# Power.net
KiCad netlist of a schematic drawn in Altium Designer
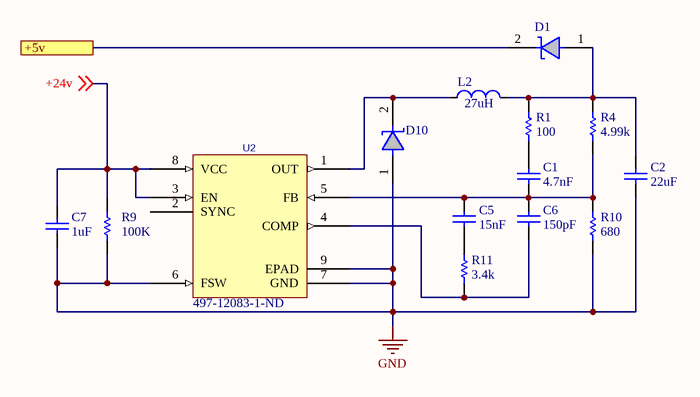
[diagram p0: Power.SchDoc]

(export (version "E")
  (design (tool "Eeschema 10.0.6"))
  (components
    (comp (ref "C1")
      (value "4.7nF")
      (footprint "0603")
      (description "4.7nF 10% 50V")
      (fields (field (name "TOLERANCE") "10%") (field (name "VOLTAGE") "50V"))
      (libsource (lib "CPHComponentSource") (part "CAP_2"))
    )
    (comp (ref "C2")
      (value "22uF")
      (footprint "0603")
      (description "22uF 20% 6.3V")
      (fields (field (name "TOLERANCE") "20%") (field (name "VOLTAGE") "6.3V"))
      (libsource (lib "CPHComponentSource") (part "CAP_1_25"))
    )
    (comp (ref "C5")
      (value "15nF")
      (footprint "0603")
      (description "15nF 10% 50V")
      (fields (field (name "TOLERANCE") "10%") (field (name "VOLTAGE") "50V"))
      (libsource (lib "CPHComponentSource") (part "CAP_1_17"))
    )
    (comp (ref "C6")
      (value "150pF")
      (footprint "0402")
      (description "150pF 5% 50V")
      (fields (field (name "TOLERANCE") "5%") (field (name "VOLTAGE") "50V"))
      (libsource (lib "CPHComponentSource") (part "CAP_1_16"))
    )
    (comp (ref "C7")
      (value "1uF")
      (footprint "0402")
      (description "1uF 10% 50V")
      (fields (field (name "Comment") "CAP_1_21_3"))
      (libsource (lib "CPHComponentSource") (part "CAP_1_21_3"))
    )
    (comp (ref "D1")
      (value "SCHOTTKY DIODE")
      (footprint "SOD323")
      (libsource (lib "CPHComponentSource") (part "SCHOTTKY DIODE"))
    )
    (comp (ref "D10")
      (value "SCHOTTKY DIODE")
      (footprint "SOD323")
      (libsource (lib "") (part "SCHOTTKY DIODE_1"))
    )
    (comp (ref "L2")
      (value "INDUCTOR")
      (footprint "0603")
      (fields (field (name "INDUCTANCE") "27uH"))
      (libsource (lib "CPHComponentSource") (part "INDUCTOR"))
    )
    (comp (ref "R1")
      (value "100")
      (footprint "0603")
      (description "RES 100 0.1W ±1% 0603 (1608)")
      (fields (field (name "Comment") "RES_9"))
      (libsource (lib "CPHComponentSource") (part "RES_9"))
    )
    (comp (ref "R4")
      (value "4.99k")
      (footprint "0402")
      (description "RES 4.99K ±1% 0603 (1608)")
      (fields (field (name "Comment") "RES_38"))
      (libsource (lib "CPHComponentSource") (part "RES_38"))
    )
    (comp (ref "R9")
      (value "100K")
      (footprint "0402")
      (description "RES 100K 0.1W ±1% 0603 (1608 Metric)")
      (fields (field (name "Comment") "RES_11"))
      (libsource (lib "CPHComponentSource") (part "RES_11"))
    )
    (comp (ref "R10")
      (value "680")
      (footprint "0402")
      (description "RES 680 ±1% 0603 (1608)")
      (fields (field (name "Comment") "RES_49"))
      (libsource (lib "CPHComponentSource") (part "RES_49"))
    )
    (comp (ref "R11")
      (value "3.4k")
      (footprint "0603")
      (description "RES 3.4K ±1% 0603 (1608)")
      (fields (field (name "Comment") "RES_32"))
      (libsource (lib "CPHComponentSource") (part "RES_32"))
    )
    (comp (ref "U2")
      (value "L7986ATR")
      (footprint "L7986ATR")
      (description "IC Switching Regulator 3A STEP-DOWN 8-HSOP")
      (fields (field (name "SUPPLIER PART NUMBER 1") "497-12083-1-ND"))
      (libsource (lib "CPHComponentSource") (part "L7986ATR"))
    )
  )
  (nets
    (net (code "1") (name "+24v") (class "Default")
      (node (ref "C7") (pin "2") (pinfunction "2_2") (pintype "passive"))
      (node (ref "R9") (pin "1") (pinfunction "1_1") (pintype "passive"))
      (node (ref "U2") (pin "3") (pinfunction "EN_3") (pintype "input"))
      (node (ref "U2") (pin "8") (pinfunction "VCC_8") (pintype "input"))
    )
    (net (code "2") (name "/+5v") (class "Default")
      (node (ref "D1") (pin "2") (pinfunction "K_2") (pintype "passive"))
    )
    (net (code "3") (name "GND") (class "Default")
      (node (ref "C2") (pin "1") (pinfunction "1_1") (pintype "passive"))
      (node (ref "C7") (pin "1") (pinfunction "1_1") (pintype "passive"))
      (node (ref "D10") (pin "1") (pinfunction "A_1") (pintype "passive"))
      (node (ref "R10") (pin "1") (pinfunction "1_1") (pintype "passive"))
      (node (ref "R9") (pin "2") (pinfunction "2_2") (pintype "passive"))
      (node (ref "U2") (pin "6") (pinfunction "FSW_6") (pintype "input"))
      (node (ref "U2") (pin "7") (pinfunction "GND_7") (pintype "power_in"))
      (node (ref "U2") (pin "9") (pinfunction "EPAD_9") (pintype "power_in"))
    )
    (net (code "4") (name "Net-(C1-Pad1)") (class "Default")
      (node (ref "C1") (pin "1") (pinfunction "1_1") (pintype "passive"))
      (node (ref "R1") (pin "1") (pinfunction "1_1") (pintype "passive"))
    )
    (net (code "5") (name "Net-(C5-Pad1)") (class "Default")
      (node (ref "C5") (pin "1") (pinfunction "1_1") (pintype "passive"))
      (node (ref "R11") (pin "2") (pinfunction "2_2") (pintype "passive"))
    )
    (net (code "6") (name "Net-(D1-A)") (class "Default")
      (node (ref "C2") (pin "2") (pinfunction "2_2") (pintype "passive"))
      (node (ref "D1") (pin "1") (pinfunction "A_1") (pintype "passive"))
      (node (ref "L2") (pin "2") (pintype "passive"))
      (node (ref "R1") (pin "2") (pinfunction "2_2") (pintype "passive"))
      (node (ref "R4") (pin "2") (pinfunction "2_2") (pintype "passive"))
    )
    (net (code "7") (name "Net-(D10-K)") (class "Default")
      (node (ref "D10") (pin "2") (pinfunction "K_2") (pintype "passive"))
      (node (ref "L2") (pin "1") (pintype "passive"))
      (node (ref "U2") (pin "1") (pinfunction "OUT_1") (pintype "output"))
    )
    (net (code "8") (name "Net-(U2-COMP)") (class "Default")
      (node (ref "C6") (pin "1") (pinfunction "1_1") (pintype "passive"))
      (node (ref "R11") (pin "1") (pinfunction "1_1") (pintype "passive"))
      (node (ref "U2") (pin "4") (pinfunction "COMP_4") (pintype "output"))
    )
    (net (code "9") (name "Net-(U2-FB)") (class "Default")
      (node (ref "C1") (pin "2") (pinfunction "2_2") (pintype "passive"))
      (node (ref "C5") (pin "2") (pinfunction "2_2") (pintype "passive"))
      (node (ref "C6") (pin "2") (pinfunction "2_2") (pintype "passive"))
      (node (ref "R10") (pin "2") (pinfunction "2_2") (pintype "passive"))
      (node (ref "R4") (pin "1") (pinfunction "1_1") (pintype "passive"))
      (node (ref "U2") (pin "5") (pinfunction "FB_5") (pintype "input"))
    )
    (net (code "10") (name "unconnected-(U2-SYNC-Pad2)") (class "Default")
      (node (ref "U2") (pin "2") (pinfunction "SYNC_2") (pintype "passive"))
    )
  )
)
